# pic16f84a.net
KiCad netlist of a schematic drawn in EAGLE
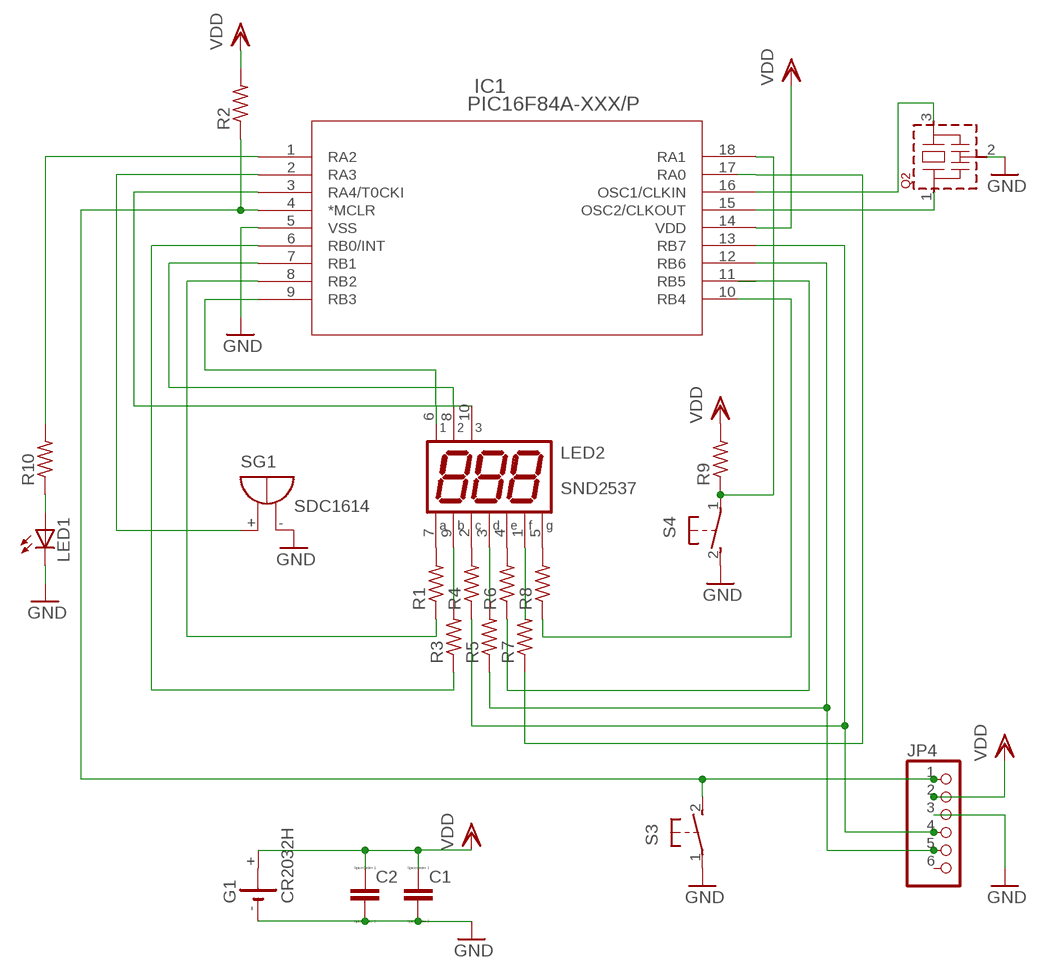
[diagram p0: schematic, sheet 1]

(export (version "E")
  (design (tool "Eeschema 10.0.6"))
  (components
    (comp (ref "C1")
      (value "C-EU050-025X075")
      (footprint "eagle-import:C050-025X075")
      (libsource (lib "eagle-import") (part "C-EU050-025X075"))
    )
    (comp (ref "C2")
      (value "C-EU050-025X075")
      (footprint "eagle-import:C050-025X075")
      (libsource (lib "eagle-import") (part "C-EU050-025X075"))
    )
    (comp (ref "G1")
      (value "CR2032H")
      (footprint "eagle-import:CR2032H")
      (libsource (lib "eagle-import") (part "CR2032H"))
    )
    (comp (ref "IC1")
      (value "PIC16F84A-XXX/P")
      (footprint "eagle-import:PDIP18_300MC")
      (libsource (lib "eagle-import") (part "PIC16F84A-XXX/P"))
    )
    (comp (ref "JP4")
      (value "PINHD-1X6")
      (footprint "eagle-import:1X06")
      (libsource (lib "eagle-import") (part "PINHD-1X6"))
    )
    (comp (ref "LED1")
      (value "LED3MM")
      (footprint "eagle-import:LED3MM")
      (libsource (lib "eagle-import") (part "LED3MM"))
    )
    (comp (ref "LED2")
      (value "SND2537")
      (footprint "eagle-import:SND2537-PKG")
      (libsource (lib "eagle-import") (part "SND2537"))
    )
    (comp (ref "Q2")
      (value "CSTLS_X")
      (footprint "eagle-import:CSTLS_X")
      (libsource (lib "eagle-import") (part "CSTLS_X"))
    )
    (comp (ref "R1")
      (value "R-US_0207/10")
      (footprint "eagle-import:0207_10")
      (libsource (lib "eagle-import") (part "R-US_0207/10"))
    )
    (comp (ref "R2")
      (value "R-US_0207/10")
      (footprint "eagle-import:0207_10")
      (libsource (lib "eagle-import") (part "R-US_0207/10"))
    )
    (comp (ref "R3")
      (value "R-US_0207/10")
      (footprint "eagle-import:0207_10")
      (libsource (lib "eagle-import") (part "R-US_0207/10"))
    )
    (comp (ref "R4")
      (value "R-US_0207/10")
      (footprint "eagle-import:0207_10")
      (libsource (lib "eagle-import") (part "R-US_0207/10"))
    )
    (comp (ref "R5")
      (value "R-US_0207/10")
      (footprint "eagle-import:0207_10")
      (libsource (lib "eagle-import") (part "R-US_0207/10"))
    )
    (comp (ref "R6")
      (value "R-US_0207/10")
      (footprint "eagle-import:0207_10")
      (libsource (lib "eagle-import") (part "R-US_0207/10"))
    )
    (comp (ref "R7")
      (value "R-US_0207/10")
      (footprint "eagle-import:0207_10")
      (libsource (lib "eagle-import") (part "R-US_0207/10"))
    )
    (comp (ref "R8")
      (value "R-US_0207/10")
      (footprint "eagle-import:0207_10")
      (libsource (lib "eagle-import") (part "R-US_0207/10"))
    )
    (comp (ref "R9")
      (value "R-US_0207/10")
      (footprint "eagle-import:0207_10")
      (libsource (lib "eagle-import") (part "R-US_0207/10"))
    )
    (comp (ref "R10")
      (value "R-US_0207/10")
      (footprint "eagle-import:0207_10")
      (libsource (lib "eagle-import") (part "R-US_0207/10"))
    )
    (comp (ref "S3")
      (value "31-XX")
      (footprint "eagle-import:B3F-31XX")
      (fields (field (name "MPN") "B3F-3100"))
      (libsource (lib "eagle-import") (part "31-XX"))
    )
    (comp (ref "S4")
      (value "31-XX")
      (footprint "eagle-import:B3F-31XX")
      (fields (field (name "MPN") "B3F-3100"))
      (libsource (lib "eagle-import") (part "31-XX"))
    )
    (comp (ref "SG1")
      (value "SDC1614")
      (footprint "eagle-import:SDC1614")
      (libsource (lib "eagle-import") (part "SDC1614"))
    )
  )
  (nets
    (net (code "1") (name "GND") (class "Default")
      (node (ref "C1") (pin "2") (pinfunction "2_2") (pintype "passive"))
      (node (ref "C2") (pin "2") (pinfunction "2_2") (pintype "passive"))
      (node (ref "G1") (pin "-") (pinfunction "-_-") (pintype "passive"))
      (node (ref "IC1") (pin "5") (pinfunction "VSS_5") (pintype "passive"))
      (node (ref "JP4") (pin "3") (pinfunction "3_3") (pintype "passive"))
      (node (ref "LED1") (pin "K") (pinfunction "C_K") (pintype "passive"))
      (node (ref "Q2") (pin "2") (pinfunction "VSS_2") (pintype "power_in"))
      (node (ref "S3") (pin "1") (pinfunction "P_1") (pintype "passive"))
      (node (ref "S4") (pin "2") (pinfunction "S_2") (pintype "passive"))
      (node (ref "SG1") (pin "-") (pinfunction "-_-") (pintype "passive"))
    )
    (net (code "2") (name "Net-(IC1-*MCLR)") (class "Default")
      (node (ref "IC1") (pin "4") (pinfunction "*MCLR_4") (pintype "passive"))
      (node (ref "JP4") (pin "1") (pinfunction "1_1") (pintype "passive"))
      (node (ref "R2") (pin "1") (pinfunction "1_1") (pintype "passive"))
      (node (ref "S3") (pin "2") (pinfunction "S_2") (pintype "passive"))
    )
    (net (code "3") (name "Net-(IC1-OSC1{slash}CLKIN)") (class "Default")
      (node (ref "IC1") (pin "16") (pinfunction "OSC1/CLKIN_16") (pintype "passive"))
      (node (ref "Q2") (pin "3") (pinfunction "3_3") (pintype "input"))
    )
    (net (code "4") (name "Net-(IC1-OSC2{slash}CLKOUT)") (class "Default")
      (node (ref "IC1") (pin "15") (pinfunction "OSC2/CLKOUT_15") (pintype "passive"))
      (node (ref "Q2") (pin "1") (pinfunction "1_1") (pintype "output"))
    )
    (net (code "5") (name "Net-(IC1-RA0)") (class "Default")
      (node (ref "IC1") (pin "17") (pinfunction "RA0_17") (pintype "passive"))
      (node (ref "R7") (pin "1") (pinfunction "1_1") (pintype "passive"))
    )
    (net (code "6") (name "Net-(IC1-RA1)") (class "Default")
      (node (ref "IC1") (pin "18") (pinfunction "RA1_18") (pintype "passive"))
      (node (ref "R9") (pin "1") (pinfunction "1_1") (pintype "passive"))
      (node (ref "S4") (pin "1") (pinfunction "P_1") (pintype "passive"))
    )
    (net (code "7") (name "Net-(IC1-RA2)") (class "Default")
      (node (ref "IC1") (pin "1") (pinfunction "RA2_1") (pintype "passive"))
      (node (ref "R10") (pin "2") (pinfunction "2_2") (pintype "passive"))
    )
    (net (code "8") (name "Net-(IC1-RA3)") (class "Default")
      (node (ref "IC1") (pin "2") (pinfunction "RA3_2") (pintype "passive"))
      (node (ref "SG1") (pin "+") (pinfunction "+_+") (pintype "passive"))
    )
    (net (code "9") (name "Net-(IC1-RA4{slash}T0CKI)") (class "Default")
      (node (ref "IC1") (pin "3") (pinfunction "RA4/T0CKI_3") (pintype "passive"))
      (node (ref "LED2") (pin "10") (pinfunction "3_10") (pintype "passive"))
    )
    (net (code "10") (name "Net-(IC1-RB0{slash}INT)") (class "Default")
      (node (ref "IC1") (pin "6") (pinfunction "RB0/INT_6") (pintype "passive"))
      (node (ref "R3") (pin "1") (pinfunction "1_1") (pintype "passive"))
    )
    (net (code "11") (name "Net-(IC1-RB1)") (class "Default")
      (node (ref "IC1") (pin "7") (pinfunction "RB1_7") (pintype "passive"))
      (node (ref "LED2") (pin "8") (pinfunction "2_8") (pintype "passive"))
    )
    (net (code "12") (name "Net-(IC1-RB2)") (class "Default")
      (node (ref "IC1") (pin "8") (pinfunction "RB2_8") (pintype "passive"))
      (node (ref "R1") (pin "1") (pinfunction "1_1") (pintype "passive"))
    )
    (net (code "13") (name "Net-(IC1-RB3)") (class "Default")
      (node (ref "IC1") (pin "9") (pinfunction "RB3_9") (pintype "passive"))
      (node (ref "LED2") (pin "6") (pinfunction "1_6") (pintype "passive"))
    )
    (net (code "14") (name "Net-(IC1-RB4)") (class "Default")
      (node (ref "IC1") (pin "10") (pinfunction "RB4_10") (pintype "passive"))
      (node (ref "R8") (pin "1") (pinfunction "1_1") (pintype "passive"))
    )
    (net (code "15") (name "Net-(IC1-RB5)") (class "Default")
      (node (ref "IC1") (pin "11") (pinfunction "RB5_11") (pintype "passive"))
      (node (ref "R6") (pin "1") (pinfunction "1_1") (pintype "passive"))
    )
    (net (code "16") (name "Net-(IC1-RB6)") (class "Default")
      (node (ref "IC1") (pin "12") (pinfunction "RB6_12") (pintype "passive"))
      (node (ref "JP4") (pin "5") (pinfunction "5_5") (pintype "passive"))
      (node (ref "R5") (pin "1") (pinfunction "1_1") (pintype "passive"))
    )
    (net (code "17") (name "Net-(IC1-RB7)") (class "Default")
      (node (ref "IC1") (pin "13") (pinfunction "RB7_13") (pintype "passive"))
      (node (ref "JP4") (pin "4") (pinfunction "4_4") (pintype "passive"))
      (node (ref "R4") (pin "1") (pinfunction "1_1") (pintype "passive"))
    )
    (net (code "18") (name "Net-(LED1-PadA)") (class "Default")
      (node (ref "LED1") (pin "A") (pinfunction "A_A") (pintype "passive"))
      (node (ref "R10") (pin "1") (pinfunction "1_1") (pintype "passive"))
    )
    (net (code "19") (name "Net-(LED2-A)") (class "Default")
      (node (ref "LED2") (pin "7") (pinfunction "A_7") (pintype "passive"))
      (node (ref "R1") (pin "2") (pinfunction "2_2") (pintype "passive"))
    )
    (net (code "20") (name "Net-(LED2-B)") (class "Default")
      (node (ref "LED2") (pin "9") (pinfunction "B_9") (pintype "passive"))
      (node (ref "R3") (pin "2") (pinfunction "2_2") (pintype "passive"))
    )
    (net (code "21") (name "Net-(LED2-C)") (class "Default")
      (node (ref "LED2") (pin "2") (pinfunction "C_2") (pintype "passive"))
      (node (ref "R4") (pin "2") (pinfunction "2_2") (pintype "passive"))
    )
    (net (code "22") (name "Net-(LED2-D)") (class "Default")
      (node (ref "LED2") (pin "3") (pinfunction "D_3") (pintype "passive"))
      (node (ref "R5") (pin "2") (pinfunction "2_2") (pintype "passive"))
    )
    (net (code "23") (name "Net-(LED2-E)") (class "Default")
      (node (ref "LED2") (pin "4") (pinfunction "E_4") (pintype "passive"))
      (node (ref "R6") (pin "2") (pinfunction "2_2") (pintype "passive"))
    )
    (net (code "24") (name "Net-(LED2-F)") (class "Default")
      (node (ref "LED2") (pin "1") (pinfunction "F_1") (pintype "passive"))
      (node (ref "R7") (pin "2") (pinfunction "2_2") (pintype "passive"))
    )
    (net (code "25") (name "Net-(LED2-G)") (class "Default")
      (node (ref "LED2") (pin "5") (pinfunction "G_5") (pintype "passive"))
      (node (ref "R8") (pin "2") (pinfunction "2_2") (pintype "passive"))
    )
    (net (code "26") (name "VDD") (class "Default")
      (node (ref "C1") (pin "1") (pinfunction "1_1") (pintype "passive"))
      (node (ref "C2") (pin "1") (pinfunction "1_1") (pintype "passive"))
      (node (ref "G1") (pin "+") (pinfunction "+_+") (pintype "passive"))
      (node (ref "IC1") (pin "14") (pinfunction "VDD_14") (pintype "passive"))
      (node (ref "JP4") (pin "2") (pinfunction "2_2") (pintype "passive"))
      (node (ref "R2") (pin "2") (pinfunction "2_2") (pintype "passive"))
      (node (ref "R9") (pin "2") (pinfunction "2_2") (pintype "passive"))
    )
    (net (code "27") (name "unconnected-(JP4-Pad6)") (class "Default")
      (node (ref "JP4") (pin "6") (pinfunction "6_6") (pintype "passive"))
    )
  )
)
